# Page07_CPU_PHY.net
KiCad netlist of a schematic drawn in Altium Designer
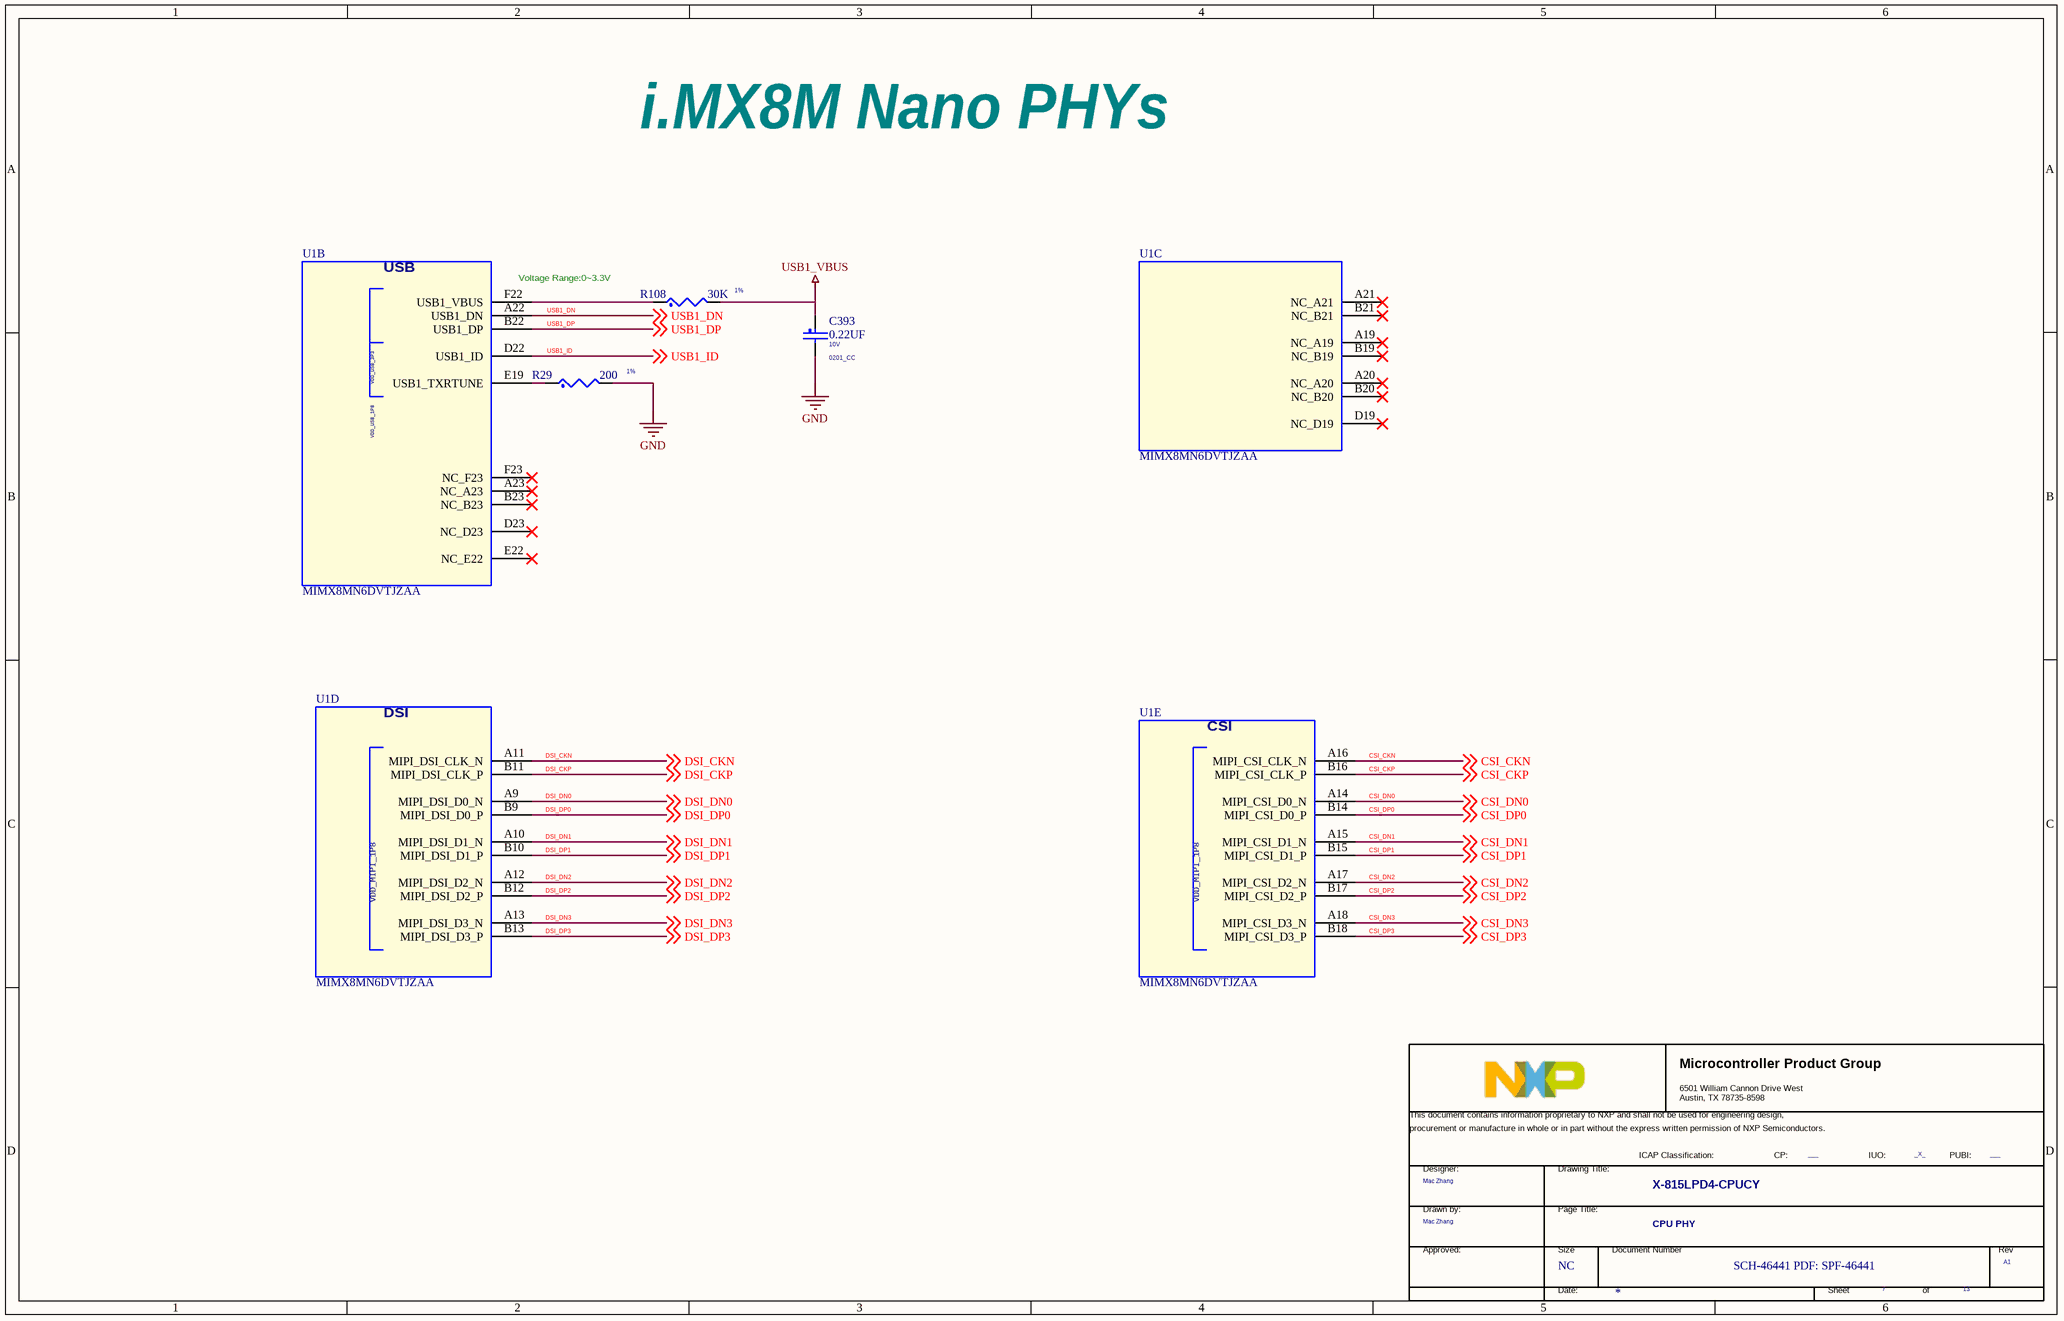
[diagram p0: Page07 CPU PHY.SchDoc]

(export (version "E")
  (design (tool "Eeschema 10.0.6"))
  (components
    (comp (ref "*")
      (value "TitleBlock_MCPG")
      (fields
        (field (name "DOC") "SCH-46441 PDF: SPF-46441")
        (field (name "REVCODE") "A1")
        (field (name "TITLE") "X-815LPD4-CPUCY")
        (field (name "PAGE SIZE") "NC")
        (field (name "PAGE NUMBER") "7")
        (field (name "PAGE COUNT") "13")
        (field (name "PAGETITLE") "CPU PHY")
        (field (name "DESIGNER") "Mac Zhang")
        (field (name "DRAWNBY") "Mac Zhang")
        (field (name "PUBI") "___")
        (field (name "FIUO") "_X_")
        (field (name "FCP") "___")
      )
      (libsource (lib "*") (part "TitleBlock_MCPG"))
    )
    (comp (ref "C393")
      (value "0.22UF")
      (footprint "0201_CC")
      (description "CAP CER 0.22UF 10V 20% X5R 0201")
      (fields
        (field (name "VOLTAGE") "10V")
        (field (name "TOLERANCE") "20%")
        (field (name "PCB FOOTPRINT") "0201_CC")
      )
      (libsource (lib "*") (part "CAP_NP"))
    )
    (comp (ref "R29")
      (value "200")
      (footprint "0201_CC")
      (description "RES MF 200 OHM 1/20W 1% 0201")
      (fields (field (name "TOLERANCE") "1%") (field (name "VOLTAGE") "25V"))
      (libsource (lib "*") (part "RES"))
    )
    (comp (ref "R108")
      (value "30K")
      (footprint "0201_CC")
      (description "RES MF 30K 1/20W 1% 0201")
      (fields (field (name "TOLERANCE") "1%") (field (name "VOLTAGE") "25V"))
      (libsource (lib "*") (part "RES"))
    )
    (comp (ref "U1")
      (value "MIMX8MN6DVTJZAA")
      (footprint "bga486_0p5_14x14")
      (description "IC CPU QUAD CORTEX A53+M7 1.5GHZ BGA486")
      (libsource (lib "*") (part "MIMX8NN_BGA486P"))
    )
  )
  (nets
    (net (code "1") (name "CSI_CKN") (class "Default")
      (node (ref "U1") (pin "A16") (pinfunction "MIPI_CSI_CLK_N_A16") (pintype "passive"))
    )
    (net (code "2") (name "CSI_CKP") (class "Default")
      (node (ref "U1") (pin "B16") (pinfunction "MIPI_CSI_CLK_P_B16") (pintype "passive"))
    )
    (net (code "3") (name "CSI_DN0") (class "Default")
      (node (ref "U1") (pin "A14") (pinfunction "MIPI_CSI_D0_N_A14") (pintype "passive"))
    )
    (net (code "4") (name "CSI_DN1") (class "Default")
      (node (ref "U1") (pin "A15") (pinfunction "MIPI_CSI_D1_N_A15") (pintype "passive"))
    )
    (net (code "5") (name "CSI_DN2") (class "Default")
      (node (ref "U1") (pin "A17") (pinfunction "MIPI_CSI_D2_N_A17") (pintype "passive"))
    )
    (net (code "6") (name "CSI_DN3") (class "Default")
      (node (ref "U1") (pin "A18") (pinfunction "MIPI_CSI_D3_N_A18") (pintype "passive"))
    )
    (net (code "7") (name "CSI_DP0") (class "Default")
      (node (ref "U1") (pin "B14") (pinfunction "MIPI_CSI_D0_P_B14") (pintype "passive"))
    )
    (net (code "8") (name "CSI_DP1") (class "Default")
      (node (ref "U1") (pin "B15") (pinfunction "MIPI_CSI_D1_P_B15") (pintype "passive"))
    )
    (net (code "9") (name "CSI_DP2") (class "Default")
      (node (ref "U1") (pin "B17") (pinfunction "MIPI_CSI_D2_P_B17") (pintype "passive"))
    )
    (net (code "10") (name "CSI_DP3") (class "Default")
      (node (ref "U1") (pin "B18") (pinfunction "MIPI_CSI_D3_P_B18") (pintype "passive"))
    )
    (net (code "11") (name "DSI_CKN") (class "Default")
      (node (ref "U1") (pin "A11") (pinfunction "MIPI_DSI_CLK_N_A11") (pintype "passive"))
    )
    (net (code "12") (name "DSI_CKP") (class "Default")
      (node (ref "U1") (pin "B11") (pinfunction "MIPI_DSI_CLK_P_B11") (pintype "passive"))
    )
    (net (code "13") (name "DSI_DN0") (class "Default")
      (node (ref "U1") (pin "A9") (pinfunction "MIPI_DSI_D0_N_A9") (pintype "passive"))
    )
    (net (code "14") (name "DSI_DN1") (class "Default")
      (node (ref "U1") (pin "A10") (pinfunction "MIPI_DSI_D1_N_A10") (pintype "passive"))
    )
    (net (code "15") (name "DSI_DN2") (class "Default")
      (node (ref "U1") (pin "A12") (pinfunction "MIPI_DSI_D2_N_A12") (pintype "passive"))
    )
    (net (code "16") (name "DSI_DN3") (class "Default")
      (node (ref "U1") (pin "A13") (pinfunction "MIPI_DSI_D3_N_A13") (pintype "passive"))
    )
    (net (code "17") (name "DSI_DP0") (class "Default")
      (node (ref "U1") (pin "B9") (pinfunction "MIPI_DSI_D0_P_B9") (pintype "passive"))
    )
    (net (code "18") (name "DSI_DP1") (class "Default")
      (node (ref "U1") (pin "B10") (pinfunction "MIPI_DSI_D1_P_B10") (pintype "passive"))
    )
    (net (code "19") (name "DSI_DP2") (class "Default")
      (node (ref "U1") (pin "B12") (pinfunction "MIPI_DSI_D2_P_B12") (pintype "passive"))
    )
    (net (code "20") (name "DSI_DP3") (class "Default")
      (node (ref "U1") (pin "B13") (pinfunction "MIPI_DSI_D3_P_B13") (pintype "passive"))
    )
    (net (code "21") (name "GND") (class "Default")
      (node (ref "C393") (pin "2") (pinfunction "2_2") (pintype "passive"))
      (node (ref "R29") (pin "2") (pinfunction "2_2") (pintype "passive"))
    )
    (net (code "22") (name "Net-(U1B-USB1_TXRTUNE)") (class "Default")
      (node (ref "R29") (pin "1") (pinfunction "1_1") (pintype "passive"))
      (node (ref "U1") (pin "E19") (pinfunction "USB1_TXRTUNE_E19") (pintype "passive"))
    )
    (net (code "23") (name "Net-(U1B-USB1_VBUS)") (class "Default")
      (node (ref "R108") (pin "1") (pinfunction "1_1") (pintype "passive"))
      (node (ref "U1") (pin "F22") (pinfunction "USB1_VBUS_F22") (pintype "passive"))
    )
    (net (code "24") (name "USB1_DN") (class "Default")
      (node (ref "U1") (pin "A22") (pinfunction "USB1_DN_A22") (pintype "passive"))
    )
    (net (code "25") (name "USB1_DP") (class "Default")
      (node (ref "U1") (pin "B22") (pinfunction "USB1_DP_B22") (pintype "passive"))
    )
    (net (code "26") (name "USB1_ID") (class "Default")
      (node (ref "U1") (pin "D22") (pinfunction "USB1_ID_D22") (pintype "passive"))
    )
    (net (code "27") (name "USB1_VBUS") (class "Default")
      (node (ref "C393") (pin "1") (pinfunction "1_1") (pintype "passive"))
      (node (ref "R108") (pin "2") (pinfunction "2_2") (pintype "passive"))
    )
    (net (code "28") (name "unconnected-(U1B-NC_A23-PadA23)") (class "Default")
      (node (ref "U1") (pin "A23") (pinfunction "NC_A23_A23") (pintype "passive+no_connect"))
    )
    (net (code "29") (name "unconnected-(U1B-NC_B23-PadB23)") (class "Default")
      (node (ref "U1") (pin "B23") (pinfunction "NC_B23_B23") (pintype "passive+no_connect"))
    )
    (net (code "30") (name "unconnected-(U1B-NC_D23-PadD23)") (class "Default")
      (node (ref "U1") (pin "D23") (pinfunction "NC_D23_D23") (pintype "passive+no_connect"))
    )
    (net (code "31") (name "unconnected-(U1B-NC_E22-PadE22)") (class "Default")
      (node (ref "U1") (pin "E22") (pinfunction "NC_E22_E22") (pintype "passive+no_connect"))
    )
    (net (code "32") (name "unconnected-(U1B-NC_F23-PadF23)") (class "Default")
      (node (ref "U1") (pin "F23") (pinfunction "NC_F23_F23") (pintype "passive+no_connect"))
    )
    (net (code "33") (name "unconnected-(U1C-NC_A19-PadA19)") (class "Default")
      (node (ref "U1") (pin "A19") (pinfunction "NC_A19_A19") (pintype "passive+no_connect"))
    )
    (net (code "34") (name "unconnected-(U1C-NC_A20-PadA20)") (class "Default")
      (node (ref "U1") (pin "A20") (pinfunction "NC_A20_A20") (pintype "passive+no_connect"))
    )
    (net (code "35") (name "unconnected-(U1C-NC_A21-PadA21)") (class "Default")
      (node (ref "U1") (pin "A21") (pinfunction "NC_A21_A21") (pintype "passive+no_connect"))
    )
    (net (code "36") (name "unconnected-(U1C-NC_B19-PadB19)") (class "Default")
      (node (ref "U1") (pin "B19") (pinfunction "NC_B19_B19") (pintype "passive+no_connect"))
    )
    (net (code "37") (name "unconnected-(U1C-NC_B20-PadB20)") (class "Default")
      (node (ref "U1") (pin "B20") (pinfunction "NC_B20_B20") (pintype "passive+no_connect"))
    )
    (net (code "38") (name "unconnected-(U1C-NC_B21-PadB21)") (class "Default")
      (node (ref "U1") (pin "B21") (pinfunction "NC_B21_B21") (pintype "passive+no_connect"))
    )
    (net (code "39") (name "unconnected-(U1C-NC_D19-PadD19)") (class "Default")
      (node (ref "U1") (pin "D19") (pinfunction "NC_D19_D19") (pintype "passive+no_connect"))
    )
  )
)
